# Sheet5.net
KiCad netlist of a schematic drawn in Altium Designer
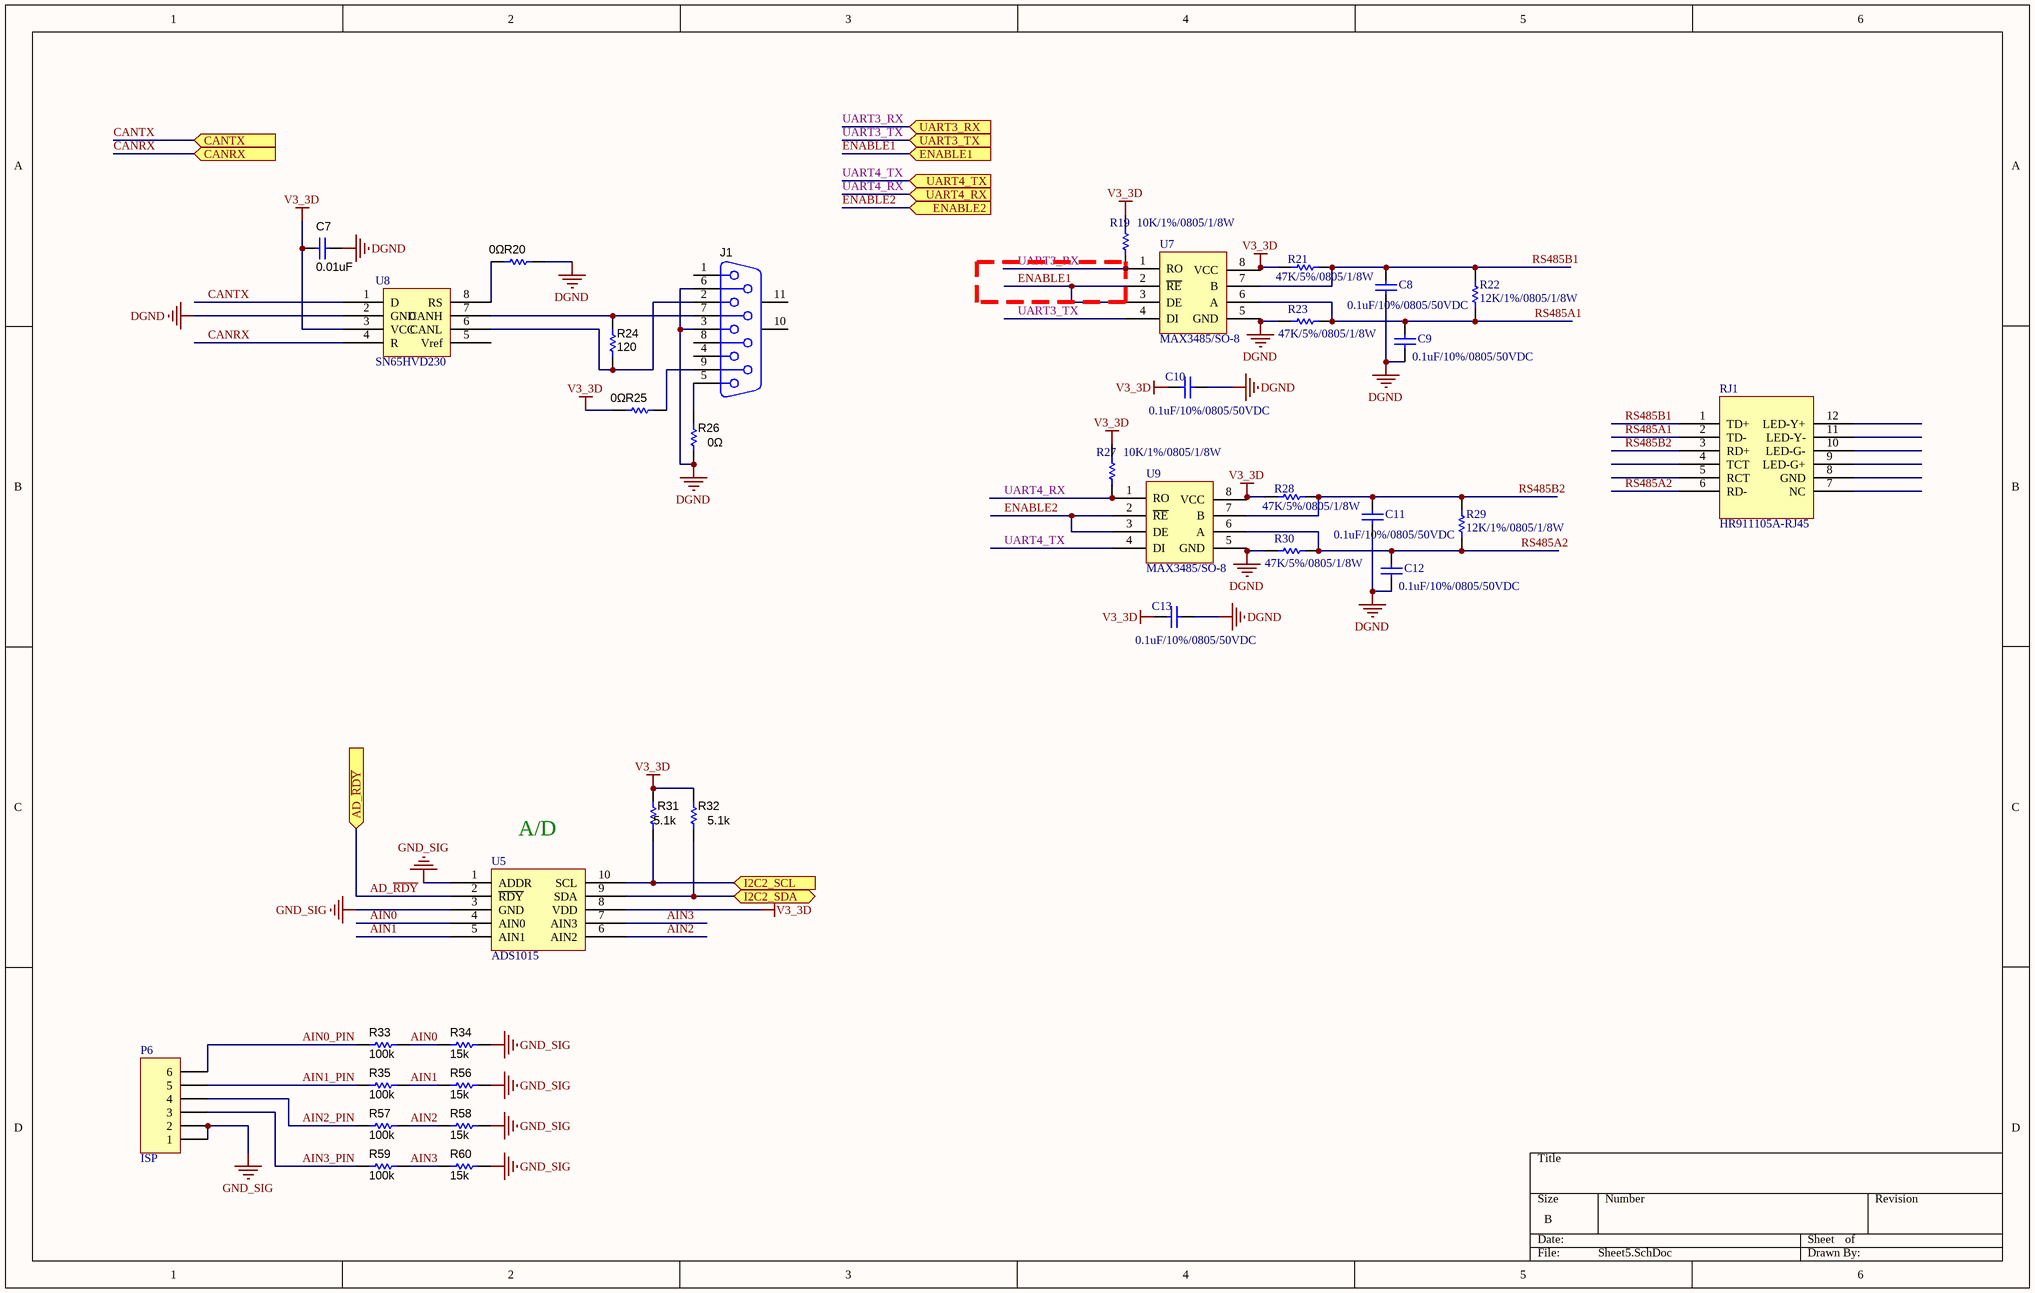
[diagram p0: Sheet5.SchDoc]

(export (version "E")
  (design (tool "Eeschema 10.0.6"))
  (components
    (comp (ref "C7")
      (value "0.01uF")
      (footprint "0805_cap")
      (description "CAP, CERM, 0.01uF, 16V, +/-10%, X7R, 0402")
      (fields
        (field (name "PARTNUMBER") "C1005X7R1C103K")
        (field (name "VALUEDISPLAYED") "0.01uF")
        (field (name "MANUFACTURER") "TDK")
        (field (name "PUBLISHER") "Texas Instruments")
      )
      (libsource (lib "Capacitor_Ceramic") (part "C1005X7R1C103K"))
    )
    (comp (ref "C8")
      (value "0.1uF/10%/0805/50VDC")
      (footprint "0805_cap")
      (libsource (lib "浙江关西电机数据库") (part "CAP_Non-polarity"))
    )
    (comp (ref "C9")
      (value "0.1uF/10%/0805/50VDC")
      (footprint "0805_cap")
      (libsource (lib "浙江关西电机数据库") (part "CAP_Non-polarity"))
    )
    (comp (ref "C10")
      (value "0.1uF/10%/0805/50VDC")
      (footprint "0805_cap")
      (libsource (lib "浙江关西电机数据库") (part "CAP_Non-polarity"))
    )
    (comp (ref "C11")
      (value "0.1uF/10%/0805/50VDC")
      (footprint "0805_cap")
      (libsource (lib "浙江关西电机数据库") (part "CAP_Non-polarity"))
    )
    (comp (ref "C12")
      (value "0.1uF/10%/0805/50VDC")
      (footprint "0805_cap")
      (libsource (lib "浙江关西电机数据库") (part "CAP_Non-polarity"))
    )
    (comp (ref "C13")
      (value "0.1uF/10%/0805/50VDC")
      (footprint "0805_cap")
      (libsource (lib "浙江关西电机数据库") (part "CAP_Non-polarity"))
    )
    (comp (ref "J1")
      (value "~")
      (footprint "CONN_1734348-1")
      (description "Conn D-SUB RCPT R/A 9POS GOLD/FL, TH")
      (fields
        (field (name "PARTNUMBER") "1734348-1")
        (field (name "MANUFACTURER") "TE Connectivity")
        (field (name "SYMBOLCREATOR") "a0412235")
        (field (name "PUBLISHER") "Texas Instruments")
      )
      (libsource (lib "Connectors") (part "1734348-1"))
    )
    (comp (ref "P6")
      (value "ISP")
      (footprint "SIP-6B")
      (description "Header, 6-Pin")
      (fields (field (name "PUBLISHER") "Altium Limited"))
      (libsource (lib "Miscellaneous Connectors") (part "Header 6"))
    )
    (comp (ref "R19")
      (value "10K/1%/0805/1/8W")
      (footprint "0805")
      (fields (field (name "PART NUMBER") "ASR-0028BA"))
      (libsource (lib "浙江关西电机数据库") (part "RES_1"))
    )
    (comp (ref "R20")
      (value "0Ω")
      (footprint "0805")
      (description "RES, 0 ohm, 1%, 0.125W, 0805")
      (fields
        (field (name "PARTNUMBER") "CRCW080560R4FKEA")
        (field (name "MANUFACTURER") "Vishay-Dale")
        (field (name "PUBLISHER") "Texas Instruments")
      )
      (libsource (lib "altium-import") (part "root_0_CRCW080560R4FKEA_"))
    )
    (comp (ref "R21")
      (value "47K/5%/0805/1/8W")
      (footprint "0805")
      (fields (field (name "PART NUMBER") "ASR-0134BA"))
      (libsource (lib "浙江关西电机数据库") (part "RES_1"))
    )
    (comp (ref "R22")
      (value "12K/1%/0805/1/8W")
      (footprint "0805")
      (libsource (lib "浙江关西电机数据库") (part "RES_1"))
    )
    (comp (ref "R23")
      (value "47K/5%/0805/1/8W")
      (footprint "0805")
      (fields (field (name "PART NUMBER") "ASR-0134BA"))
      (libsource (lib "浙江关西电机数据库") (part "RES_1"))
    )
    (comp (ref "R24")
      (value "120")
      (footprint "0805")
      (description "RES, 120ohm, 1%, 0.125W, 0805")
      (fields
        (field (name "PARTNUMBER") "CRCW080560R4FKEA")
        (field (name "MANUFACTURER") "Vishay-Dale")
        (field (name "PUBLISHER") "Texas Instruments")
      )
      (libsource (lib "altium-import") (part "root_3_CRCW080560R4FKEA_"))
    )
    (comp (ref "R25")
      (value "0Ω")
      (footprint "0805")
      (description "RES, 0 ohm, 1%, 0.125W, 0805")
      (fields
        (field (name "PARTNUMBER") "CRCW080560R4FKEA")
        (field (name "MANUFACTURER") "Vishay-Dale")
        (field (name "PUBLISHER") "Texas Instruments")
      )
      (libsource (lib "altium-import") (part "root_0_CRCW080560R4FKEA_"))
    )
    (comp (ref "R26")
      (value "0Ω")
      (footprint "0805")
      (description "RES, 0 ohm, 1%, 0.125W, 0805")
      (fields
        (field (name "PARTNUMBER") "CRCW080560R4FKEA")
        (field (name "MANUFACTURER") "Vishay-Dale")
        (field (name "PUBLISHER") "Texas Instruments")
      )
      (libsource (lib "altium-import") (part "root_1_CRCW080560R4FKEA_"))
    )
    (comp (ref "R27")
      (value "10K/1%/0805/1/8W")
      (footprint "0805")
      (fields (field (name "PART NUMBER") "ASR-0028BA"))
      (libsource (lib "浙江关西电机数据库") (part "RES_1"))
    )
    (comp (ref "R28")
      (value "47K/5%/0805/1/8W")
      (footprint "0805")
      (fields (field (name "PART NUMBER") "ASR-0134BA"))
      (libsource (lib "浙江关西电机数据库") (part "RES_1"))
    )
    (comp (ref "R29")
      (value "12K/1%/0805/1/8W")
      (footprint "0805")
      (libsource (lib "浙江关西电机数据库") (part "RES_1"))
    )
    (comp (ref "R30")
      (value "47K/5%/0805/1/8W")
      (footprint "0805")
      (fields (field (name "PART NUMBER") "ASR-0134BA"))
      (libsource (lib "浙江关西电机数据库") (part "RES_1"))
    )
    (comp (ref "R31")
      (value "5.1k")
      (footprint "0805")
      (description "RES, 120ohm, 1%, 0.125W, 0805")
      (fields
        (field (name "PARTNUMBER") "CRCW080560R4FKEA")
        (field (name "MANUFACTURER") "Vishay-Dale")
        (field (name "PUBLISHER") "Texas Instruments")
      )
      (libsource (lib "altium-import") (part "root_3_CRCW080560R4FKEA_"))
    )
    (comp (ref "R32")
      (value "5.1k")
      (footprint "0805")
      (description "RES, 120ohm, 1%, 0.125W, 0805")
      (fields
        (field (name "PARTNUMBER") "CRCW080560R4FKEA")
        (field (name "MANUFACTURER") "Vishay-Dale")
        (field (name "PUBLISHER") "Texas Instruments")
      )
      (libsource (lib "altium-import") (part "root_3_CRCW080560R4FKEA_"))
    )
    (comp (ref "R33")
      (value "100k")
      (footprint "0805")
      (description "RES, 120ohm, 1%, 0.125W, 0805")
      (fields
        (field (name "PARTNUMBER") "CRCW080560R4FKEA")
        (field (name "MANUFACTURER") "Vishay-Dale")
        (field (name "PUBLISHER") "Texas Instruments")
      )
      (libsource (lib "altium-import") (part "root_0_CRCW080560R4FKEA_"))
    )
    (comp (ref "R34")
      (value "15k")
      (footprint "0805")
      (description "RES, 120ohm, 1%, 0.125W, 0805")
      (fields
        (field (name "PARTNUMBER") "CRCW080560R4FKEA")
        (field (name "MANUFACTURER") "Vishay-Dale")
        (field (name "PUBLISHER") "Texas Instruments")
      )
      (libsource (lib "altium-import") (part "root_0_CRCW080560R4FKEA_"))
    )
    (comp (ref "R35")
      (value "100k")
      (footprint "0805")
      (description "RES, 120ohm, 1%, 0.125W, 0805")
      (fields
        (field (name "PARTNUMBER") "CRCW080560R4FKEA")
        (field (name "MANUFACTURER") "Vishay-Dale")
        (field (name "PUBLISHER") "Texas Instruments")
      )
      (libsource (lib "altium-import") (part "root_0_CRCW080560R4FKEA_"))
    )
    (comp (ref "R56")
      (value "15k")
      (footprint "0805")
      (description "RES, 120ohm, 1%, 0.125W, 0805")
      (fields
        (field (name "PARTNUMBER") "CRCW080560R4FKEA")
        (field (name "MANUFACTURER") "Vishay-Dale")
        (field (name "PUBLISHER") "Texas Instruments")
      )
      (libsource (lib "altium-import") (part "root_0_CRCW080560R4FKEA_"))
    )
    (comp (ref "R57")
      (value "100k")
      (footprint "0805")
      (description "RES, 120ohm, 1%, 0.125W, 0805")
      (fields
        (field (name "PARTNUMBER") "CRCW080560R4FKEA")
        (field (name "MANUFACTURER") "Vishay-Dale")
        (field (name "PUBLISHER") "Texas Instruments")
      )
      (libsource (lib "altium-import") (part "root_0_CRCW080560R4FKEA_"))
    )
    (comp (ref "R58")
      (value "15k")
      (footprint "0805")
      (description "RES, 120ohm, 1%, 0.125W, 0805")
      (fields
        (field (name "PARTNUMBER") "CRCW080560R4FKEA")
        (field (name "MANUFACTURER") "Vishay-Dale")
        (field (name "PUBLISHER") "Texas Instruments")
      )
      (libsource (lib "altium-import") (part "root_0_CRCW080560R4FKEA_"))
    )
    (comp (ref "R59")
      (value "100k")
      (footprint "0805")
      (description "RES, 120ohm, 1%, 0.125W, 0805")
      (fields
        (field (name "PARTNUMBER") "CRCW080560R4FKEA")
        (field (name "MANUFACTURER") "Vishay-Dale")
        (field (name "PUBLISHER") "Texas Instruments")
      )
      (libsource (lib "altium-import") (part "root_0_CRCW080560R4FKEA_"))
    )
    (comp (ref "R60")
      (value "15k")
      (footprint "0805")
      (description "RES, 120ohm, 1%, 0.125W, 0805")
      (fields
        (field (name "PARTNUMBER") "CRCW080560R4FKEA")
        (field (name "MANUFACTURER") "Vishay-Dale")
        (field (name "PUBLISHER") "Texas Instruments")
      )
      (libsource (lib "altium-import") (part "root_0_CRCW080560R4FKEA_"))
    )
    (comp (ref "RJ1")
      (value "HR911105A-RJ45")
      (footprint "HR911105A")
      (libsource (lib "moonlight") (part "HR911105A-RJ45"))
    )
    (comp (ref "U5") (value "ADS1015") (footprint "MUB10A_N") (libsource (lib "dolphi_ecs") (part "ADS1015")))
    (comp (ref "U7")
      (value "MAX3485/SO-8")
      (footprint "SO-G8")
      (libsource (lib "SCHLIBRARIES") (part "MAX485"))
    )
    (comp (ref "U8")
      (value "SN65HVD230")
      (footprint "SO-G8")
      (libsource (lib "SCHLIBRARIES") (part "SN65HVD230"))
    )
    (comp (ref "U9")
      (value "MAX3485/SO-8")
      (footprint "SO-G8")
      (libsource (lib "SCHLIBRARIES") (part "MAX485"))
    )
  )
  (nets
    (net (code "1") (name "/AD_~{RDY}") (class "Default")
      (node (ref "U5") (pin "2") (pinfunction "~{RDY}_2") (pintype "passive"))
    )
    (net (code "2") (name "/AIN0") (class "Default")
      (node (ref "R33") (pin "2") (pinfunction "2_2") (pintype "passive"))
      (node (ref "R34") (pin "1") (pinfunction "1_1") (pintype "passive"))
      (node (ref "U5") (pin "4") (pinfunction "AIN0_4") (pintype "passive"))
    )
    (net (code "3") (name "/AIN0_PIN") (class "Default")
      (node (ref "P6") (pin "6") (pinfunction "6_6") (pintype "passive"))
      (node (ref "R33") (pin "1") (pinfunction "1_1") (pintype "passive"))
    )
    (net (code "4") (name "/AIN1") (class "Default")
      (node (ref "R35") (pin "2") (pinfunction "2_2") (pintype "passive"))
      (node (ref "R56") (pin "1") (pinfunction "1_1") (pintype "passive"))
      (node (ref "U5") (pin "5") (pinfunction "AIN1_5") (pintype "passive"))
    )
    (net (code "5") (name "/AIN1_PIN") (class "Default")
      (node (ref "P6") (pin "5") (pinfunction "5_5") (pintype "passive"))
      (node (ref "R35") (pin "1") (pinfunction "1_1") (pintype "passive"))
    )
    (net (code "6") (name "/AIN2") (class "Default")
      (node (ref "R57") (pin "2") (pinfunction "2_2") (pintype "passive"))
      (node (ref "R58") (pin "1") (pinfunction "1_1") (pintype "passive"))
      (node (ref "U5") (pin "6") (pinfunction "AIN2_6") (pintype "passive"))
    )
    (net (code "7") (name "/AIN2_PIN") (class "Default")
      (node (ref "P6") (pin "4") (pinfunction "4_4") (pintype "passive"))
      (node (ref "R57") (pin "1") (pinfunction "1_1") (pintype "passive"))
    )
    (net (code "8") (name "/AIN3") (class "Default")
      (node (ref "R59") (pin "2") (pinfunction "2_2") (pintype "passive"))
      (node (ref "R60") (pin "1") (pinfunction "1_1") (pintype "passive"))
      (node (ref "U5") (pin "7") (pinfunction "AIN3_7") (pintype "passive"))
    )
    (net (code "9") (name "/AIN3_PIN") (class "Default")
      (node (ref "P6") (pin "3") (pinfunction "3_3") (pintype "passive"))
      (node (ref "R59") (pin "1") (pinfunction "1_1") (pintype "passive"))
    )
    (net (code "10") (name "/CANRX") (class "Default")
      (node (ref "U8") (pin "4") (pinfunction "R_4") (pintype "passive"))
    )
    (net (code "11") (name "/CANTX") (class "Default")
      (node (ref "U8") (pin "1") (pinfunction "D_1") (pintype "passive"))
    )
    (net (code "12") (name "/ENABLE1") (class "Default")
      (node (ref "U7") (pin "2") (pinfunction "~{RE}_2") (pintype "passive"))
      (node (ref "U7") (pin "3") (pinfunction "DE_3") (pintype "passive"))
    )
    (net (code "13") (name "/ENABLE2") (class "Default")
      (node (ref "U9") (pin "2") (pinfunction "~{RE}_2") (pintype "passive"))
      (node (ref "U9") (pin "3") (pinfunction "DE_3") (pintype "passive"))
    )
    (net (code "14") (name "/I2C2_SCL") (class "Default")
      (node (ref "R31") (pin "2") (pinfunction "2_2") (pintype "passive"))
      (node (ref "U5") (pin "10") (pinfunction "SCL_10") (pintype "passive"))
    )
    (net (code "15") (name "/I2C2_SDA") (class "Default")
      (node (ref "R32") (pin "2") (pinfunction "2_2") (pintype "passive"))
      (node (ref "U5") (pin "9") (pinfunction "SDA_9") (pintype "passive"))
    )
    (net (code "16") (name "/RS485A1") (class "Default")
      (node (ref "C9") (pin "2") (pinfunction "2_2") (pintype "passive"))
      (node (ref "R22") (pin "1") (pinfunction "1_1") (pintype "passive"))
      (node (ref "R23") (pin "1") (pinfunction "1_1") (pintype "passive"))
      (node (ref "RJ1") (pin "2") (pinfunction "TD-_2") (pintype "passive"))
      (node (ref "U7") (pin "6") (pinfunction "A_6") (pintype "passive"))
    )
    (net (code "17") (name "/RS485A2") (class "Default")
      (node (ref "C12") (pin "2") (pinfunction "2_2") (pintype "passive"))
      (node (ref "R29") (pin "1") (pinfunction "1_1") (pintype "passive"))
      (node (ref "R30") (pin "1") (pinfunction "1_1") (pintype "passive"))
      (node (ref "RJ1") (pin "6") (pinfunction "RD-_6") (pintype "passive"))
      (node (ref "U9") (pin "6") (pinfunction "A_6") (pintype "passive"))
    )
    (net (code "18") (name "/RS485B1") (class "Default")
      (node (ref "C8") (pin "2") (pinfunction "2_2") (pintype "passive"))
      (node (ref "R21") (pin "1") (pinfunction "1_1") (pintype "passive"))
      (node (ref "R22") (pin "2") (pinfunction "2_2") (pintype "passive"))
      (node (ref "RJ1") (pin "1") (pinfunction "TD+_1") (pintype "passive"))
      (node (ref "U7") (pin "7") (pinfunction "B_7") (pintype "passive"))
    )
    (net (code "19") (name "/RS485B2") (class "Default")
      (node (ref "C11") (pin "2") (pinfunction "2_2") (pintype "passive"))
      (node (ref "R28") (pin "1") (pinfunction "1_1") (pintype "passive"))
      (node (ref "R29") (pin "2") (pinfunction "2_2") (pintype "passive"))
      (node (ref "RJ1") (pin "3") (pinfunction "RD+_3") (pintype "passive"))
      (node (ref "U9") (pin "7") (pinfunction "B_7") (pintype "passive"))
    )
    (net (code "20") (name "/UART3_RX") (class "Default")
      (node (ref "R19") (pin "1") (pinfunction "1_1") (pintype "passive"))
      (node (ref "U7") (pin "1") (pinfunction "RO_1") (pintype "passive"))
    )
    (net (code "21") (name "/UART3_TX") (class "Default")
      (node (ref "U7") (pin "4") (pinfunction "DI_4") (pintype "passive"))
    )
    (net (code "22") (name "/UART4_RX") (class "Default")
      (node (ref "R27") (pin "1") (pinfunction "1_1") (pintype "passive"))
      (node (ref "U9") (pin "1") (pinfunction "RO_1") (pintype "passive"))
    )
    (net (code "23") (name "/UART4_TX") (class "Default")
      (node (ref "U9") (pin "4") (pinfunction "DI_4") (pintype "passive"))
    )
    (net (code "24") (name "DGND") (class "Default")
      (node (ref "C10") (pin "2") (pinfunction "2_2") (pintype "passive"))
      (node (ref "C11") (pin "1") (pinfunction "1_1") (pintype "passive"))
      (node (ref "C12") (pin "1") (pinfunction "1_1") (pintype "passive"))
      (node (ref "C13") (pin "2") (pinfunction "2_2") (pintype "passive"))
      (node (ref "C7") (pin "2") (pinfunction "2_2") (pintype "passive"))
      (node (ref "C8") (pin "1") (pinfunction "1_1") (pintype "passive"))
      (node (ref "C9") (pin "1") (pinfunction "1_1") (pintype "passive"))
      (node (ref "J1") (pin "3") (pinfunction "3_3") (pintype "passive"))
      (node (ref "J1") (pin "6") (pinfunction "6_6") (pintype "passive"))
      (node (ref "R20") (pin "2") (pinfunction "2_2") (pintype "passive"))
      (node (ref "R23") (pin "2") (pinfunction "2_2") (pintype "passive"))
      (node (ref "R26") (pin "1") (pinfunction "1_1") (pintype "passive"))
      (node (ref "R30") (pin "2") (pinfunction "2_2") (pintype "passive"))
      (node (ref "U7") (pin "5") (pinfunction "GND_5") (pintype "passive"))
      (node (ref "U8") (pin "2") (pinfunction "GND_2") (pintype "passive"))
      (node (ref "U9") (pin "5") (pinfunction "GND_5") (pintype "passive"))
    )
    (net (code "25") (name "GND_SIG") (class "Default")
      (node (ref "P6") (pin "1") (pinfunction "1_1") (pintype "passive"))
      (node (ref "P6") (pin "2") (pinfunction "2_2") (pintype "passive"))
      (node (ref "R34") (pin "2") (pinfunction "2_2") (pintype "passive"))
      (node (ref "R56") (pin "2") (pinfunction "2_2") (pintype "passive"))
      (node (ref "R58") (pin "2") (pinfunction "2_2") (pintype "passive"))
      (node (ref "R60") (pin "2") (pinfunction "2_2") (pintype "passive"))
      (node (ref "U5") (pin "1") (pinfunction "ADDR_1") (pintype "passive"))
      (node (ref "U5") (pin "3") (pinfunction "GND_3") (pintype "power_in"))
    )
    (net (code "26") (name "Net-(J1-Pad5)") (class "Default")
      (node (ref "J1") (pin "5") (pinfunction "5_5") (pintype "passive"))
      (node (ref "R26") (pin "2") (pinfunction "2_2") (pintype "passive"))
    )
    (net (code "27") (name "Net-(J1-Pad9)") (class "Default")
      (node (ref "J1") (pin "9") (pinfunction "9_9") (pintype "passive"))
      (node (ref "R25") (pin "2") (pinfunction "2_2") (pintype "passive"))
    )
    (net (code "28") (name "Net-(U8-CANH)") (class "Default")
      (node (ref "J1") (pin "7") (pinfunction "7_7") (pintype "passive"))
      (node (ref "R24") (pin "1") (pinfunction "1_1") (pintype "passive"))
      (node (ref "U8") (pin "7") (pinfunction "CANH_7") (pintype "passive"))
    )
    (net (code "29") (name "Net-(U8-CANL)") (class "Default")
      (node (ref "J1") (pin "2") (pinfunction "2_2") (pintype "passive"))
      (node (ref "R24") (pin "2") (pinfunction "2_2") (pintype "passive"))
      (node (ref "U8") (pin "6") (pinfunction "CANL_6") (pintype "passive"))
    )
    (net (code "30") (name "Net-(U8-RS)") (class "Default")
      (node (ref "R20") (pin "1") (pinfunction "1_1") (pintype "passive"))
      (node (ref "U8") (pin "8") (pinfunction "RS_8") (pintype "passive"))
    )
    (net (code "31") (name "V3_3D") (class "Default")
      (node (ref "C10") (pin "1") (pinfunction "1_1") (pintype "passive"))
      (node (ref "C13") (pin "1") (pinfunction "1_1") (pintype "passive"))
      (node (ref "C7") (pin "1") (pinfunction "1_1") (pintype "passive"))
      (node (ref "R19") (pin "2") (pinfunction "2_2") (pintype "passive"))
      (node (ref "R21") (pin "2") (pinfunction "2_2") (pintype "passive"))
      (node (ref "R25") (pin "1") (pinfunction "1_1") (pintype "passive"))
      (node (ref "R27") (pin "2") (pinfunction "2_2") (pintype "passive"))
      (node (ref "R28") (pin "2") (pinfunction "2_2") (pintype "passive"))
      (node (ref "R31") (pin "1") (pinfunction "1_1") (pintype "passive"))
      (node (ref "R32") (pin "1") (pinfunction "1_1") (pintype "passive"))
      (node (ref "U5") (pin "8") (pinfunction "VDD_8") (pintype "power_in"))
      (node (ref "U7") (pin "8") (pinfunction "VCC_8") (pintype "passive"))
      (node (ref "U8") (pin "3") (pinfunction "VCC_3") (pintype "passive"))
      (node (ref "U9") (pin "8") (pinfunction "VCC_8") (pintype "passive"))
    )
    (net (code "32") (name "unconnected-(J1-MH1-Pad10)") (class "Default")
      (node (ref "J1") (pin "10") (pinfunction "MH1_10") (pintype "passive"))
    )
    (net (code "33") (name "unconnected-(J1-MH2-Pad11)") (class "Default")
      (node (ref "J1") (pin "11") (pinfunction "MH2_11") (pintype "passive"))
    )
    (net (code "34") (name "unconnected-(J1-Pad1)") (class "Default")
      (node (ref "J1") (pin "1") (pinfunction "1_1") (pintype "passive"))
    )
    (net (code "35") (name "unconnected-(J1-Pad4)") (class "Default")
      (node (ref "J1") (pin "4") (pinfunction "4_4") (pintype "passive"))
    )
    (net (code "36") (name "unconnected-(J1-Pad8)") (class "Default")
      (node (ref "J1") (pin "8") (pinfunction "8_8") (pintype "passive"))
    )
    (net (code "37") (name "unconnected-(RJ1-GND-Pad8)") (class "Default")
      (node (ref "RJ1") (pin "8") (pinfunction "GND_8") (pintype "passive"))
    )
    (net (code "38") (name "unconnected-(RJ1-LED-G+-Pad9)") (class "Default")
      (node (ref "RJ1") (pin "9") (pinfunction "LED-G+_9") (pintype "passive"))
    )
    (net (code "39") (name "unconnected-(RJ1-LED-G--Pad10)") (class "Default")
      (node (ref "RJ1") (pin "10") (pinfunction "LED-G-_10") (pintype "passive"))
    )
    (net (code "40") (name "unconnected-(RJ1-LED-Y+-Pad12)") (class "Default")
      (node (ref "RJ1") (pin "12") (pinfunction "LED-Y+_12") (pintype "passive"))
    )
    (net (code "41") (name "unconnected-(RJ1-LED-Y--Pad11)") (class "Default")
      (node (ref "RJ1") (pin "11") (pinfunction "LED-Y-_11") (pintype "passive"))
    )
    (net (code "42") (name "unconnected-(RJ1-NC-Pad7)") (class "Default")
      (node (ref "RJ1") (pin "7") (pinfunction "NC_7") (pintype "passive"))
    )
    (net (code "43") (name "unconnected-(RJ1-RCT-Pad5)") (class "Default")
      (node (ref "RJ1") (pin "5") (pinfunction "RCT_5") (pintype "passive"))
    )
    (net (code "44") (name "unconnected-(RJ1-TCT-Pad4)") (class "Default")
      (node (ref "RJ1") (pin "4") (pinfunction "TCT_4") (pintype "passive"))
    )
    (net (code "45") (name "unconnected-(U8-Vref-Pad5)") (class "Default")
      (node (ref "U8") (pin "5") (pinfunction "Vref_5") (pintype "passive"))
    )
  )
)
